# RPi_Zero_W_Breakout_1_0.net
KiCad netlist of a schematic drawn in EAGLE
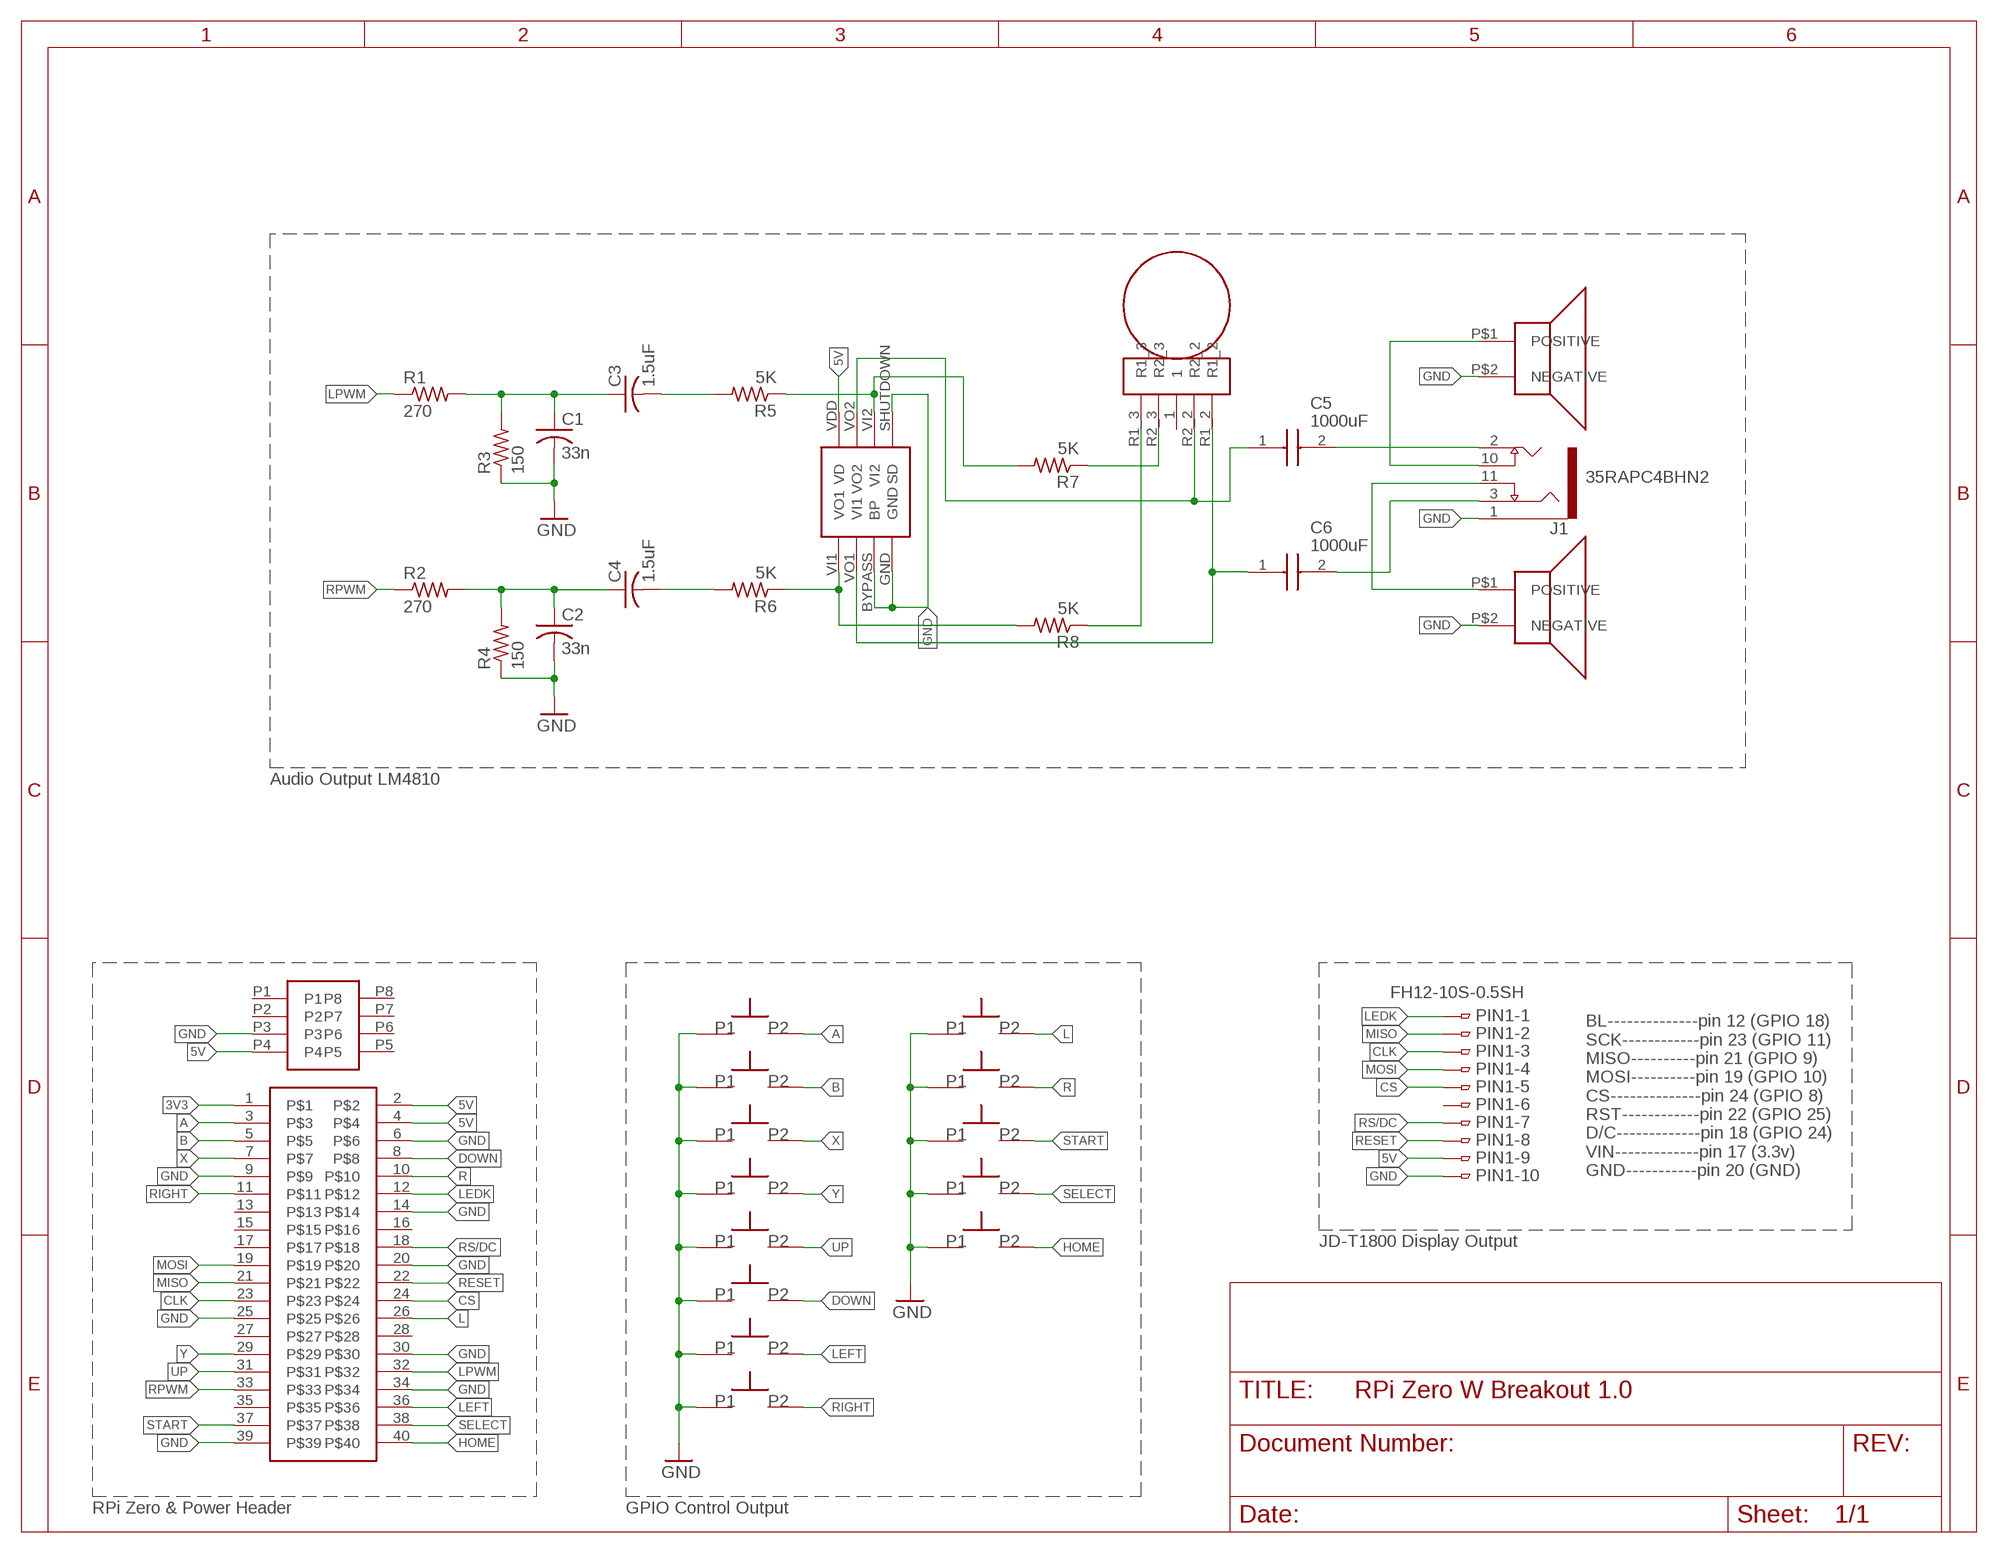
[diagram p0: schematic, sheet 1]

(export (version "E")
  (design (tool "Eeschema 10.0.6"))
  (components
    (comp (ref "A")
      (value "SPST_TACTILE_SWITCH")
      (footprint "eagle-import:SPST_TACTILESWITCH_TL3301PF160QG")
      (libsource (lib "eagle-import") (part "SPST_TACTILE_SWITCH"))
    )
    (comp (ref "B")
      (value "SPST_TACTILESWITCH_TL3301PF160QG")
      (footprint "eagle-import:SPST_TACTILESWITCH_TL3301PF160QG")
      (libsource (lib "eagle-import") (part "SPST_TACTILESWITCH_TL3301PF160QG"))
    )
    (comp (ref "C1")
      (value "33n")
      (footprint "eagle-import:C0805K")
      (libsource (lib "eagle-import") (part "C-USC0805K"))
    )
    (comp (ref "C2")
      (value "33n")
      (footprint "eagle-import:C0805K")
      (libsource (lib "eagle-import") (part "C-USC0805K"))
    )
    (comp (ref "C3")
      (value "1.5uF")
      (footprint "eagle-import:C0805K")
      (libsource (lib "eagle-import") (part "C-USC0805K"))
    )
    (comp (ref "C4")
      (value "1.5uF")
      (footprint "eagle-import:C0805K")
      (libsource (lib "eagle-import") (part "C-USC0805K"))
    )
    (comp (ref "C5")
      (value "1000uF")
      (footprint "eagle-import:UWT(8X10)")
      (fields
        (field (name "MANUFACTURER_PART_NUMBER") "UWT0J102MNL1GS")
        (field (name "MOUSER_PART_NUMBER") "647-UWT0J102MNL1S")
      )
      (libsource (lib "eagle-import") (part "UWT0J102MNL1GS"))
    )
    (comp (ref "C6")
      (value "1000uF")
      (footprint "eagle-import:UWT(8X10)")
      (fields
        (field (name "MANUFACTURER_PART_NUMBER") "UWT0J102MNL1GS")
        (field (name "MOUSER_PART_NUMBER") "647-UWT0J102MNL1S")
      )
      (libsource (lib "eagle-import") (part "UWT0J102MNL1GS"))
    )
    (comp (ref "DOWN")
      (value "SPST_TACTILESWITCH_TL3301PF160QG")
      (footprint "eagle-import:SPST_TACTILESWITCH_TL3301PF160QG")
      (libsource (lib "eagle-import") (part "SPST_TACTILESWITCH_TL3301PF160QG"))
    )
    (comp (ref "HOME")
      (value "SPST_TACTILESWITCH_TL3301PF160QG")
      (footprint "eagle-import:SPST_TACTILESWITCH_TL3301PF160QG")
      (libsource (lib "eagle-import") (part "SPST_TACTILESWITCH_TL3301PF160QG"))
    )
    (comp (ref "J1")
      (value "35RAPC4BHN2")
      (footprint "eagle-import:SWITCHCRAFT_35RAPC4BHN2")
      (fields (field (name "DIGI-KEY_PART_NUMBER") "SC1459-ND") (field (name "MF") "Switchcraft"))
      (libsource (lib "eagle-import") (part "35RAPC4BHN2"))
    )
    (comp (ref "LEFT")
      (value "SPST_TACTILESWITCH_TL3301PF160QG")
      (footprint "eagle-import:SPST_TACTILESWITCH_TL3301PF160QG")
      (libsource (lib "eagle-import") (part "SPST_TACTILESWITCH_TL3301PF160QG"))
    )
    (comp (ref "LSPK")
      (value "SP-1208")
      (footprint "eagle-import:SP-1208")
      (libsource (lib "eagle-import") (part "SP-1208"))
    )
    (comp (ref "PIN1")
      (value "FH12-10S-0.5SH")
      (footprint "eagle-import:FH12-10S-0.5SH")
      (fields (field (name "MPN") "FH12-10S-0.5SH(55)"))
      (libsource (lib "eagle-import") (part "FH12-10S-0.5SH"))
    )
    (comp (ref "R1")
      (value "270")
      (footprint "eagle-import:R0805")
      (libsource (lib "eagle-import") (part "R-US_R0805"))
    )
    (comp (ref "R2")
      (value "270")
      (footprint "eagle-import:R0805")
      (libsource (lib "eagle-import") (part "R-US_R0805"))
    )
    (comp (ref "R3")
      (value "150")
      (footprint "eagle-import:R0805")
      (libsource (lib "eagle-import") (part "R-US_R0805"))
    )
    (comp (ref "R4")
      (value "150")
      (footprint "eagle-import:R0805")
      (libsource (lib "eagle-import") (part "R-US_R0805"))
    )
    (comp (ref "R5")
      (value "5K")
      (footprint "eagle-import:R0805")
      (libsource (lib "eagle-import") (part "R-US_R0805"))
    )
    (comp (ref "R6")
      (value "5K")
      (footprint "eagle-import:R0805")
      (libsource (lib "eagle-import") (part "R-US_R0805"))
    )
    (comp (ref "R7")
      (value "5K")
      (footprint "eagle-import:R0805")
      (libsource (lib "eagle-import") (part "R-US_R0805"))
    )
    (comp (ref "R8")
      (value "5K")
      (footprint "eagle-import:R0805")
      (libsource (lib "eagle-import") (part "R-US_R0805"))
    )
    (comp (ref "RF")
      (value "RK14J12A0A0K")
      (footprint "eagle-import:RK14J12A0A0K")
      (libsource (lib "eagle-import") (part "RK14J12A0A0K"))
    )
    (comp (ref "RIGHT")
      (value "SPST_TACTILESWITCH_TL3301PF160QG")
      (footprint "eagle-import:SPST_TACTILESWITCH_TL3301PF160QG")
      (libsource (lib "eagle-import") (part "SPST_TACTILESWITCH_TL3301PF160QG"))
    )
    (comp (ref "RSPK")
      (value "SP-1208")
      (footprint "eagle-import:SP-1208")
      (libsource (lib "eagle-import") (part "SP-1208"))
    )
    (comp (ref "SELECT")
      (value "SPST_TACTILESWITCH_TL3301PF160QG")
      (footprint "eagle-import:SPST_TACTILESWITCH_TL3301PF160QG")
      (libsource (lib "eagle-import") (part "SPST_TACTILESWITCH_TL3301PF160QG"))
    )
    (comp (ref "START")
      (value "SPST_TACTILE_SWITCH")
      (footprint "eagle-import:SPST_TACTILESWITCH_TL3301PF160QG")
      (libsource (lib "eagle-import") (part "SPST_TACTILE_SWITCH"))
    )
    (comp (ref "U$1")
      (value "RPI_ZERO")
      (footprint "eagle-import:RPI_ZERO")
      (libsource (lib "eagle-import") (part "RPI_ZERO"))
    )
    (comp (ref "U$2")
      (value "LM4810MM/NOPBCT-ND")
      (footprint "eagle-import:NOPBCT-ND")
      (libsource (lib "eagle-import") (part "LM4810MM/NOPBCT-ND"))
    )
    (comp (ref "U$3")
      (value "M22-6340442")
      (footprint "eagle-import:M22-6340442")
      (libsource (lib "eagle-import") (part "M22-6340442"))
    )
    (comp (ref "U$4")
      (value "SPST_TACTILE_SWITCHRIGHTANGLEBENT")
      (footprint "eagle-import:SPST_TACTILESWITCH_TL3360CF185Q_BENTFRAME")
      (fields (field (name "SPICEPREFIX") "B"))
      (libsource (lib "eagle-import") (part "SPST_TACTILE_SWITCHRIGHTANGLEBENT"))
    )
    (comp (ref "U$5")
      (value "SPST_TACTILE_SWITCHRIGHTANGLEBENT")
      (footprint "eagle-import:SPST_TACTILESWITCH_TL3360CF185Q_BENTFRAME")
      (fields (field (name "SPICEPREFIX") "B"))
      (libsource (lib "eagle-import") (part "SPST_TACTILE_SWITCHRIGHTANGLEBENT"))
    )
    (comp (ref "UP")
      (value "SPST_TACTILESWITCH_TL3301PF160QG")
      (footprint "eagle-import:SPST_TACTILESWITCH_TL3301PF160QG")
      (libsource (lib "eagle-import") (part "SPST_TACTILESWITCH_TL3301PF160QG"))
    )
    (comp (ref "X")
      (value "SPST_TACTILESWITCH_TL3301PF160QG")
      (footprint "eagle-import:SPST_TACTILESWITCH_TL3301PF160QG")
      (libsource (lib "eagle-import") (part "SPST_TACTILESWITCH_TL3301PF160QG"))
    )
    (comp (ref "Y")
      (value "SPST_TACTILESWITCH_TL3301PF160QG")
      (footprint "eagle-import:SPST_TACTILESWITCH_TL3301PF160QG")
      (libsource (lib "eagle-import") (part "SPST_TACTILESWITCH_TL3301PF160QG"))
    )
  )
  (nets
    (net (code "1") (name "3V3") (class "Default")
      (node (ref "U$1") (pin "1") (pinfunction "P$1_1") (pintype "bidirectional"))
    )
    (net (code "2") (name "5V") (class "Default")
      (node (ref "PIN1") (pin "9") (pinfunction "1_9") (pintype "passive"))
      (node (ref "U$1") (pin "2") (pinfunction "P$2_2") (pintype "bidirectional"))
      (node (ref "U$1") (pin "4") (pinfunction "P$4_4") (pintype "bidirectional"))
      (node (ref "U$2") (pin "VDD") (pinfunction "VD_VDD") (pintype "bidirectional"))
      (node (ref "U$3") (pin "P4") (pinfunction "P4_P4") (pintype "bidirectional"))
    )
    (net (code "3") (name "A") (class "Default")
      (node (ref "A") (pin "P$3") (pinfunction "P$2_P$3") (pintype "bidirectional"))
      (node (ref "U$1") (pin "3") (pinfunction "P$3_3") (pintype "bidirectional"))
    )
    (net (code "4") (name "B") (class "Default")
      (node (ref "B") (pin "P$3") (pinfunction "P$2_P$3") (pintype "bidirectional"))
      (node (ref "U$1") (pin "5") (pinfunction "P$5_5") (pintype "bidirectional"))
    )
    (net (code "5") (name "CLK") (class "Default")
      (node (ref "PIN1") (pin "3") (pinfunction "1_3") (pintype "passive"))
      (node (ref "U$1") (pin "23") (pinfunction "P$23_23") (pintype "bidirectional"))
    )
    (net (code "6") (name "CS") (class "Default")
      (node (ref "PIN1") (pin "5") (pinfunction "1_5") (pintype "passive"))
      (node (ref "U$1") (pin "24") (pinfunction "P$24_24") (pintype "bidirectional"))
    )
    (net (code "7") (name "DOWN") (class "Default")
      (node (ref "DOWN") (pin "P$3") (pinfunction "P$2_P$3") (pintype "bidirectional"))
      (node (ref "U$1") (pin "8") (pinfunction "P$8_8") (pintype "bidirectional"))
    )
    (net (code "8") (name "GND") (class "Default")
      (node (ref "A") (pin "P$1") (pinfunction "P$1_P$1") (pintype "bidirectional"))
      (node (ref "B") (pin "P$1") (pinfunction "P$1_P$1") (pintype "bidirectional"))
      (node (ref "C1") (pin "2") (pinfunction "2_2") (pintype "passive"))
      (node (ref "C2") (pin "2") (pinfunction "2_2") (pintype "passive"))
      (node (ref "DOWN") (pin "P$1") (pinfunction "P$1_P$1") (pintype "bidirectional"))
      (node (ref "HOME") (pin "P$1") (pinfunction "P$1_P$1") (pintype "bidirectional"))
      (node (ref "J1") (pin "1") (pinfunction "1_1") (pintype "passive"))
      (node (ref "LEFT") (pin "P$1") (pinfunction "P$1_P$1") (pintype "bidirectional"))
      (node (ref "LSPK") (pin "P$2") (pinfunction "NEGATIVE_P$2") (pintype "bidirectional"))
      (node (ref "PIN1") (pin "10") (pinfunction "1_10") (pintype "passive"))
      (node (ref "R3") (pin "1") (pinfunction "1_1") (pintype "passive"))
      (node (ref "R4") (pin "1") (pinfunction "1_1") (pintype "passive"))
      (node (ref "RIGHT") (pin "P$1") (pinfunction "P$1_P$1") (pintype "bidirectional"))
      (node (ref "RSPK") (pin "P$2") (pinfunction "NEGATIVE_P$2") (pintype "bidirectional"))
      (node (ref "SELECT") (pin "P$1") (pinfunction "P$1_P$1") (pintype "bidirectional"))
      (node (ref "START") (pin "P$1") (pinfunction "P$1_P$1") (pintype "bidirectional"))
      (node (ref "U$1") (pin "14") (pinfunction "P$14_14") (pintype "bidirectional"))
      (node (ref "U$1") (pin "20") (pinfunction "P$20_20") (pintype "bidirectional"))
      (node (ref "U$1") (pin "25") (pinfunction "P$25_25") (pintype "bidirectional"))
      (node (ref "U$1") (pin "30") (pinfunction "P$30_30") (pintype "bidirectional"))
      (node (ref "U$1") (pin "34") (pinfunction "P$34_34") (pintype "bidirectional"))
      (node (ref "U$1") (pin "39") (pinfunction "P$39_39") (pintype "bidirectional"))
      (node (ref "U$1") (pin "6") (pinfunction "P$6_6") (pintype "bidirectional"))
      (node (ref "U$1") (pin "9") (pinfunction "P$9_9") (pintype "bidirectional"))
      (node (ref "U$2") (pin "BYPASS") (pinfunction "BP_BYPASS") (pintype "bidirectional"))
      (node (ref "U$2") (pin "GND") (pinfunction "GND_GND") (pintype "bidirectional"))
      (node (ref "U$2") (pin "SHUTDOWN") (pinfunction "SD_SHUTDOWN") (pintype "bidirectional"))
      (node (ref "U$3") (pin "P3") (pinfunction "P3_P3") (pintype "bidirectional"))
      (node (ref "U$4") (pin "P$1") (pinfunction "P$1_P$1") (pintype "bidirectional"))
      (node (ref "U$5") (pin "P$1") (pinfunction "P$1_P$1") (pintype "bidirectional"))
      (node (ref "UP") (pin "P$1") (pinfunction "P$1_P$1") (pintype "bidirectional"))
      (node (ref "X") (pin "P$1") (pinfunction "P$1_P$1") (pintype "bidirectional"))
      (node (ref "Y") (pin "P$1") (pinfunction "P$1_P$1") (pintype "bidirectional"))
    )
    (net (code "9") (name "HOME") (class "Default")
      (node (ref "HOME") (pin "P$3") (pinfunction "P$2_P$3") (pintype "bidirectional"))
      (node (ref "U$1") (pin "40") (pinfunction "P$40_40") (pintype "bidirectional"))
    )
    (net (code "10") (name "L") (class "Default")
      (node (ref "U$1") (pin "26") (pinfunction "P$26_26") (pintype "bidirectional"))
      (node (ref "U$4") (pin "P$2") (pinfunction "P$2_P$2") (pintype "bidirectional"))
    )
    (net (code "11") (name "LEDK") (class "Default")
      (node (ref "PIN1") (pin "1") (pinfunction "1_1") (pintype "passive"))
      (node (ref "U$1") (pin "12") (pinfunction "P$12_12") (pintype "bidirectional"))
    )
    (net (code "12") (name "LEFT") (class "Default")
      (node (ref "LEFT") (pin "P$3") (pinfunction "P$2_P$3") (pintype "bidirectional"))
      (node (ref "U$1") (pin "36") (pinfunction "P$36_36") (pintype "bidirectional"))
    )
    (net (code "13") (name "LPWM") (class "Default")
      (node (ref "R1") (pin "1") (pinfunction "1_1") (pintype "passive"))
      (node (ref "U$1") (pin "32") (pinfunction "P$32_32") (pintype "bidirectional"))
    )
    (net (code "14") (name "MISO") (class "Default")
      (node (ref "PIN1") (pin "2") (pinfunction "1_2") (pintype "passive"))
      (node (ref "U$1") (pin "21") (pinfunction "P$21_21") (pintype "bidirectional"))
    )
    (net (code "15") (name "MOSI") (class "Default")
      (node (ref "PIN1") (pin "4") (pinfunction "1_4") (pintype "passive"))
      (node (ref "U$1") (pin "19") (pinfunction "P$19_19") (pintype "bidirectional"))
    )
    (net (code "16") (name "Net-(C1-Pad1)") (class "Default")
      (node (ref "C1") (pin "1") (pinfunction "1_1") (pintype "passive"))
      (node (ref "C3") (pin "1") (pinfunction "1_1") (pintype "passive"))
      (node (ref "R1") (pin "2") (pinfunction "2_2") (pintype "passive"))
      (node (ref "R3") (pin "2") (pinfunction "2_2") (pintype "passive"))
    )
    (net (code "17") (name "Net-(C2-Pad1)") (class "Default")
      (node (ref "C2") (pin "1") (pinfunction "1_1") (pintype "passive"))
      (node (ref "C4") (pin "1") (pinfunction "1_1") (pintype "passive"))
      (node (ref "R2") (pin "2") (pinfunction "2_2") (pintype "passive"))
      (node (ref "R4") (pin "2") (pinfunction "2_2") (pintype "passive"))
    )
    (net (code "18") (name "Net-(C3-Pad2)") (class "Default")
      (node (ref "C3") (pin "2") (pinfunction "2_2") (pintype "passive"))
      (node (ref "R5") (pin "2") (pinfunction "2_2") (pintype "passive"))
    )
    (net (code "19") (name "Net-(C4-Pad2)") (class "Default")
      (node (ref "C4") (pin "2") (pinfunction "2_2") (pintype "passive"))
      (node (ref "R6") (pin "2") (pinfunction "2_2") (pintype "passive"))
    )
    (net (code "20") (name "Net-(C5-+)") (class "Default")
      (node (ref "C5") (pin "1") (pinfunction "+_1") (pintype "bidirectional"))
      (node (ref "RF") (pin "R2_2") (pinfunction "R2_2_R2_2") (pintype "bidirectional"))
      (node (ref "U$2") (pin "VO2") (pinfunction "VO2_VO2") (pintype "bidirectional"))
    )
    (net (code "21") (name "Net-(C5--)") (class "Default")
      (node (ref "C5") (pin "2") (pinfunction "-_2") (pintype "bidirectional"))
      (node (ref "J1") (pin "2") (pinfunction "2_2") (pintype "passive"))
    )
    (net (code "22") (name "Net-(C6-+)") (class "Default")
      (node (ref "C6") (pin "1") (pinfunction "+_1") (pintype "bidirectional"))
      (node (ref "RF") (pin "R1_2") (pinfunction "R1_2_R1_2") (pintype "bidirectional"))
      (node (ref "U$2") (pin "VO1") (pinfunction "VI1_VO1") (pintype "bidirectional"))
    )
    (net (code "23") (name "Net-(C6--)") (class "Default")
      (node (ref "C6") (pin "2") (pinfunction "-_2") (pintype "bidirectional"))
      (node (ref "J1") (pin "3") (pinfunction "3_3") (pintype "passive"))
    )
    (net (code "24") (name "Net-(LSPK-POSITIVE)") (class "Default")
      (node (ref "J1") (pin "10") (pinfunction "10_10") (pintype "passive"))
      (node (ref "LSPK") (pin "P$1") (pinfunction "POSITIVE_P$1") (pintype "bidirectional"))
    )
    (net (code "25") (name "Net-(R5-Pad1)") (class "Default")
      (node (ref "R5") (pin "1") (pinfunction "1_1") (pintype "passive"))
      (node (ref "R7") (pin "2") (pinfunction "2_2") (pintype "passive"))
      (node (ref "U$2") (pin "VI2") (pinfunction "VI2_VI2") (pintype "bidirectional"))
    )
    (net (code "26") (name "Net-(R7-Pad1)") (class "Default")
      (node (ref "R7") (pin "1") (pinfunction "1_1") (pintype "passive"))
      (node (ref "RF") (pin "R2_3") (pinfunction "R2_3_R2_3") (pintype "bidirectional"))
    )
    (net (code "27") (name "Net-(R8-Pad1)") (class "Default")
      (node (ref "R8") (pin "1") (pinfunction "1_1") (pintype "passive"))
      (node (ref "RF") (pin "R1_3") (pinfunction "R1_3_R1_3") (pintype "bidirectional"))
    )
    (net (code "28") (name "Net-(RSPK-POSITIVE)") (class "Default")
      (node (ref "J1") (pin "11") (pinfunction "11_11") (pintype "passive"))
      (node (ref "RSPK") (pin "P$1") (pinfunction "POSITIVE_P$1") (pintype "bidirectional"))
    )
    (net (code "29") (name "Net-(U$2-VO1)") (class "Default")
      (node (ref "R6") (pin "1") (pinfunction "1_1") (pintype "passive"))
      (node (ref "R8") (pin "2") (pinfunction "2_2") (pintype "passive"))
      (node (ref "U$2") (pin "VI1") (pinfunction "VO1_VI1") (pintype "bidirectional"))
    )
    (net (code "30") (name "R") (class "Default")
      (node (ref "U$1") (pin "10") (pinfunction "P$10_10") (pintype "bidirectional"))
      (node (ref "U$5") (pin "P$2") (pinfunction "P$2_P$2") (pintype "bidirectional"))
    )
    (net (code "31") (name "RESET") (class "Default")
      (node (ref "PIN1") (pin "8") (pinfunction "1_8") (pintype "passive"))
      (node (ref "U$1") (pin "22") (pinfunction "P$22_22") (pintype "bidirectional"))
    )
    (net (code "32") (name "RIGHT") (class "Default")
      (node (ref "RIGHT") (pin "P$3") (pinfunction "P$2_P$3") (pintype "bidirectional"))
      (node (ref "U$1") (pin "11") (pinfunction "P$11_11") (pintype "bidirectional"))
    )
    (net (code "33") (name "RPWM") (class "Default")
      (node (ref "R2") (pin "1") (pinfunction "1_1") (pintype "passive"))
      (node (ref "U$1") (pin "33") (pinfunction "P$33_33") (pintype "bidirectional"))
    )
    (net (code "34") (name "RS{slash}DC") (class "Default")
      (node (ref "PIN1") (pin "7") (pinfunction "1_7") (pintype "passive"))
      (node (ref "U$1") (pin "18") (pinfunction "P$18_18") (pintype "bidirectional"))
    )
    (net (code "35") (name "SELECT") (class "Default")
      (node (ref "SELECT") (pin "P$3") (pinfunction "P$2_P$3") (pintype "bidirectional"))
      (node (ref "U$1") (pin "38") (pinfunction "P$38_38") (pintype "bidirectional"))
    )
    (net (code "36") (name "START") (class "Default")
      (node (ref "START") (pin "P$3") (pinfunction "P$2_P$3") (pintype "bidirectional"))
      (node (ref "U$1") (pin "37") (pinfunction "P$37_37") (pintype "bidirectional"))
    )
    (net (code "37") (name "UP") (class "Default")
      (node (ref "U$1") (pin "31") (pinfunction "P$31_31") (pintype "bidirectional"))
      (node (ref "UP") (pin "P$3") (pinfunction "P$2_P$3") (pintype "bidirectional"))
    )
    (net (code "38") (name "X") (class "Default")
      (node (ref "U$1") (pin "7") (pinfunction "P$7_7") (pintype "bidirectional"))
      (node (ref "X") (pin "P$3") (pinfunction "P$2_P$3") (pintype "bidirectional"))
    )
    (net (code "39") (name "Y") (class "Default")
      (node (ref "U$1") (pin "29") (pinfunction "P$29_29") (pintype "bidirectional"))
      (node (ref "Y") (pin "P$3") (pinfunction "P$2_P$3") (pintype "bidirectional"))
    )
    (net (code "40") (name "unconnected-(PIN1G-1-Pad6)") (class "Default")
      (node (ref "PIN1") (pin "6") (pinfunction "1_6") (pintype "passive"))
    )
    (net (code "41") (name "unconnected-(RF-Pad1)") (class "Default")
      (node (ref "RF") (pin "1") (pinfunction "1_1") (pintype "bidirectional"))
    )
    (net (code "42") (name "unconnected-(U$1-P$13-Pad13)") (class "Default")
      (node (ref "U$1") (pin "13") (pinfunction "P$13_13") (pintype "bidirectional"))
    )
    (net (code "43") (name "unconnected-(U$1-P$15-Pad15)") (class "Default")
      (node (ref "U$1") (pin "15") (pinfunction "P$15_15") (pintype "bidirectional"))
    )
    (net (code "44") (name "unconnected-(U$1-P$16-Pad16)") (class "Default")
      (node (ref "U$1") (pin "16") (pinfunction "P$16_16") (pintype "bidirectional"))
    )
    (net (code "45") (name "unconnected-(U$1-P$17-Pad17)") (class "Default")
      (node (ref "U$1") (pin "17") (pinfunction "P$17_17") (pintype "bidirectional"))
    )
    (net (code "46") (name "unconnected-(U$1-P$27-Pad27)") (class "Default")
      (node (ref "U$1") (pin "27") (pinfunction "P$27_27") (pintype "bidirectional"))
    )
    (net (code "47") (name "unconnected-(U$1-P$28-Pad28)") (class "Default")
      (node (ref "U$1") (pin "28") (pinfunction "P$28_28") (pintype "bidirectional"))
    )
    (net (code "48") (name "unconnected-(U$1-P$35-Pad35)") (class "Default")
      (node (ref "U$1") (pin "35") (pinfunction "P$35_35") (pintype "bidirectional"))
    )
    (net (code "49") (name "unconnected-(U$3-PadP1)") (class "Default")
      (node (ref "U$3") (pin "P1") (pinfunction "P1_P1") (pintype "bidirectional"))
    )
    (net (code "50") (name "unconnected-(U$3-PadP2)") (class "Default")
      (node (ref "U$3") (pin "P2") (pinfunction "P2_P2") (pintype "bidirectional"))
    )
    (net (code "51") (name "unconnected-(U$3-PadP5)") (class "Default")
      (node (ref "U$3") (pin "P5") (pinfunction "P5_P5") (pintype "bidirectional"))
    )
    (net (code "52") (name "unconnected-(U$3-PadP6)") (class "Default")
      (node (ref "U$3") (pin "P6") (pinfunction "P6_P6") (pintype "bidirectional"))
    )
    (net (code "53") (name "unconnected-(U$3-PadP7)") (class "Default")
      (node (ref "U$3") (pin "P7") (pinfunction "P7_P7") (pintype "bidirectional"))
    )
    (net (code "54") (name "unconnected-(U$3-PadP8)") (class "Default")
      (node (ref "U$3") (pin "P8") (pinfunction "P8_P8") (pintype "bidirectional"))
    )
  )
)
